# Spindle_Control.net
KiCad netlist of a schematic drawn in Altium Designer
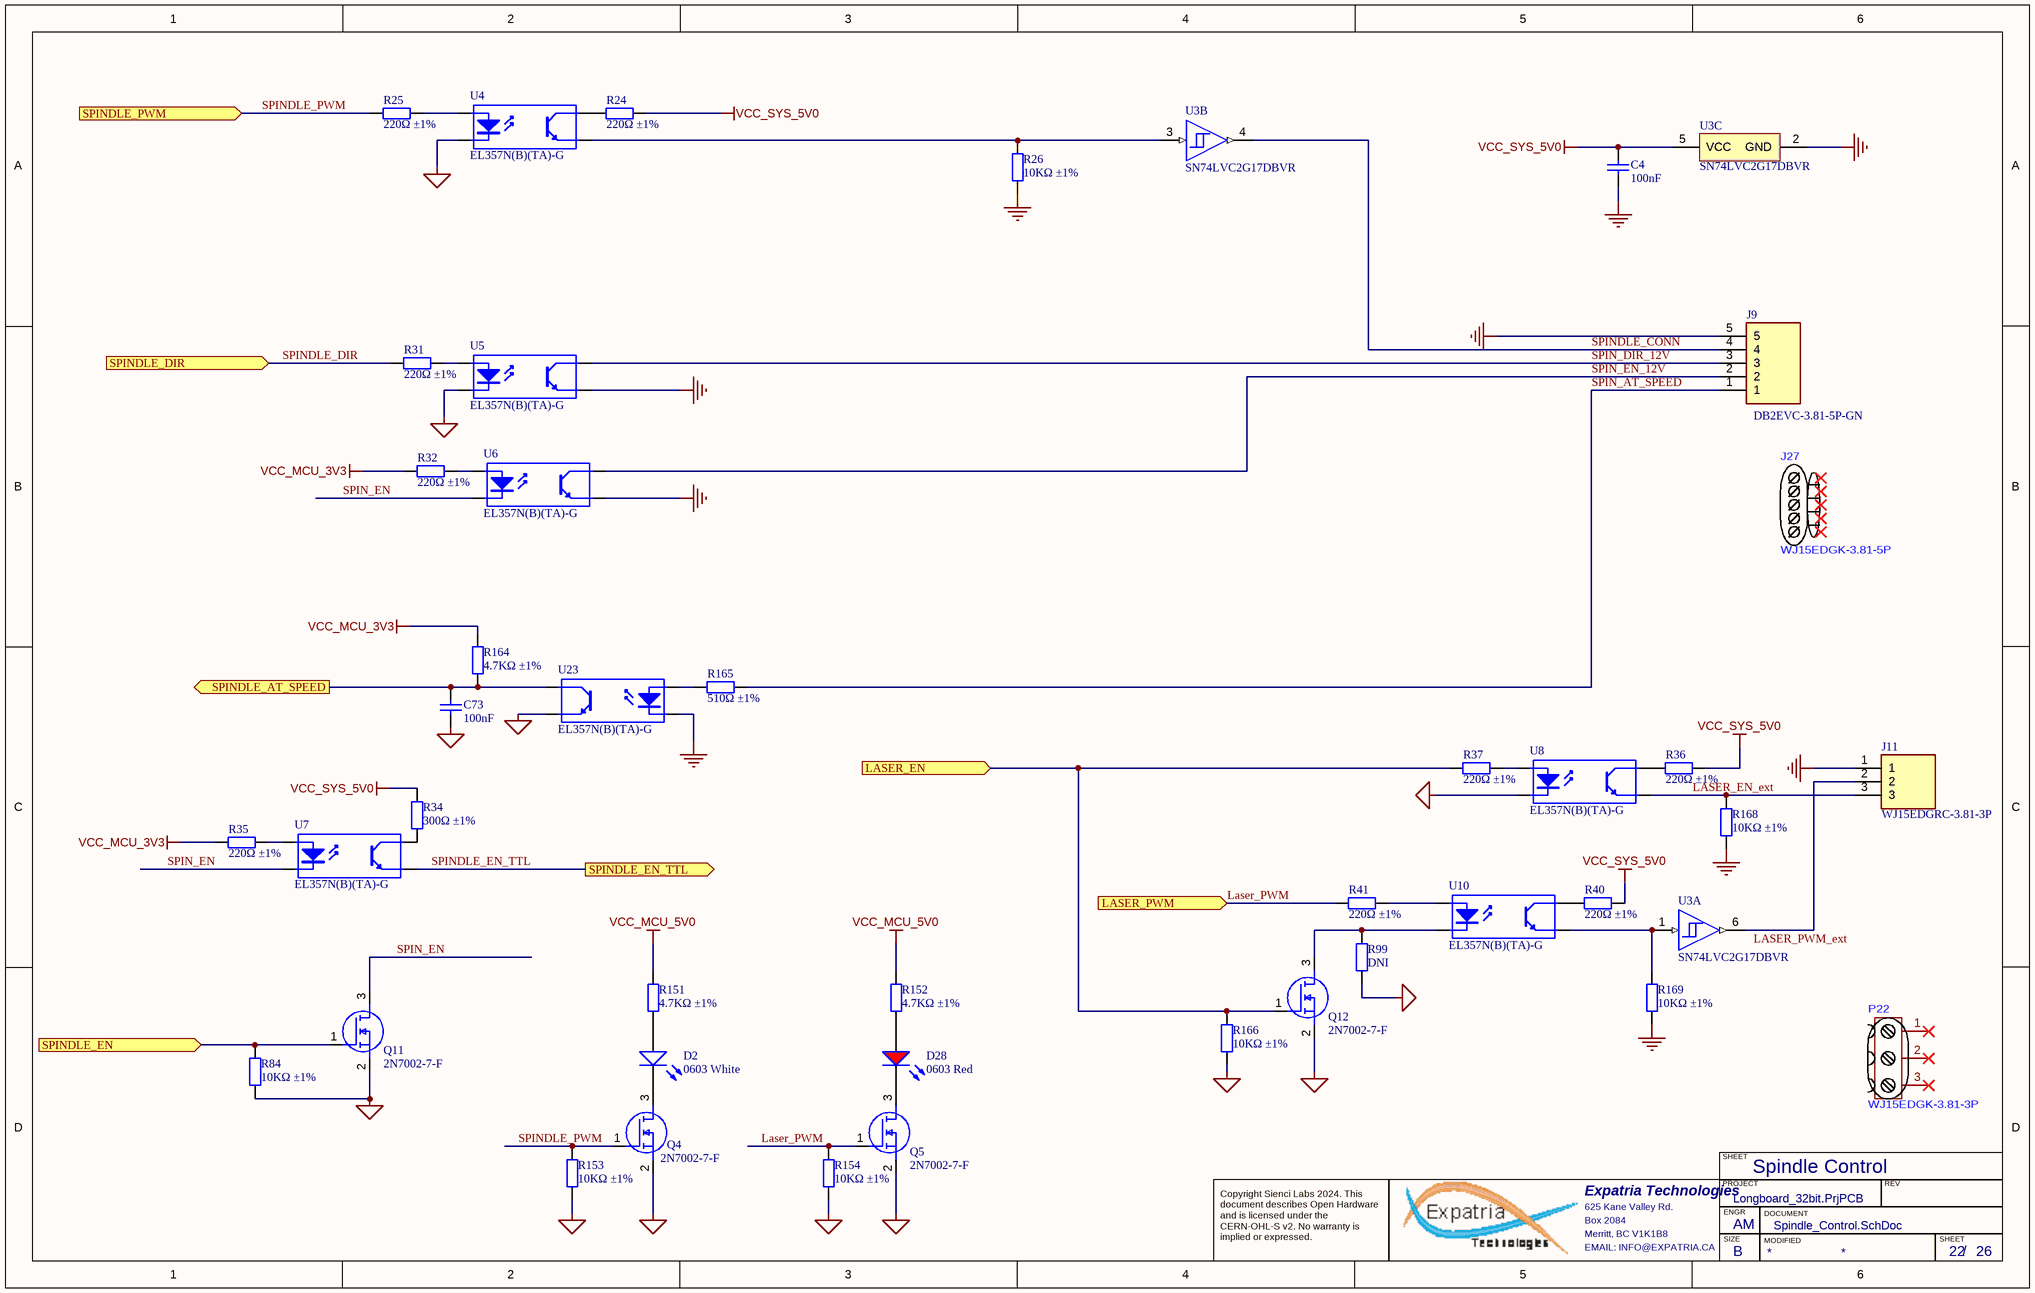
[diagram p0: Spindle_Control.SchDoc]

(export (version "E")
  (design (tool "Eeschema 10.0.6"))
  (components
    (comp (ref "C4")
      (value "100nF")
      (footprint "0603_C")
      (description "50V 100nF X7R ±10% 0603 Multilayer Ceramic Capacitors MLCC - SMD/SMT ROHS")
      (fields
        (field (name "MANUFACTURER") "YAGEO")
        (field (name "MANUFACTURER PART NUMBER") "CC0603KRX7R9BB104")
      )
      (libsource (lib "Sienci_Labs") (part "0603 100nF (104) 10% 50V"))
    )
    (comp (ref "C73")
      (value "100nF")
      (footprint "0402_C")
      (description "16V 100nF X7R ±10% 0402 Multilayer Ceramic Capacitors MLCC - SMD/SMT ROHS")
      (fields (field (name "MANUFACTURER") "Samsung Electro-Mechanics") (field (name "TOLERANCE") "10%"))
      (libsource (lib "Sienci_Labs") (part "0402 100nF (104) 10% 16V"))
    )
    (comp (ref "D2")
      (value "0603 White")
      (footprint "0603_LED_S1 - white")
      (description "LED")
      (fields
        (field (name "MANUFACTURER PART NUMBER") "19-217UWD/S365-2/TR8")
        (field (name "MANUFACTURER") "Everlight Elec")
      )
      (libsource (lib "Sienci_Labs") (part "19-217UWD/S365-2/TR8"))
    )
    (comp (ref "D28")
      (value "0603 Red")
      (footprint "0603_LED_S1")
      (fields
        (field (name "MANUFACTURER") "Everlight Elec")
        (field (name "MANUFACTURER PART NUMBER") "19-213SURC/S530-A3/TR8")
      )
      (libsource (lib "Sienci_Labs") (part "19-213SURC/S530-A3/TR8"))
    )
    (comp (ref "J9")
      (value "DB2EVC-3.81-5P-GN")
      (footprint "CONN-TH_5P-P3.81_DB2EVC-3.81-5P")
      (description "3.81mm Green Board Edge/Receptacle-Close Push-Pull,P=3.81mm Pluggable System Terminal Block ROHS")
      (fields (field (name "MANUFACTURER") "DIBO"))
      (libsource (lib "Sienci_Labs") (part "DB2EVC-3.81-5P-GN"))
    )
    (comp (ref "J11")
      (value "WJ15EDGRC-3.81-3P")
      (footprint "SHDRRA3W85P0X381_1X3_1231X915X720P")
      (description "3.81mm Green Board Edge/Receptacle-Close Push-Pull,P=3.81mm Pluggable System Terminal Block ROHS")
      (fields (field (name "MANUFACTURER") "Ningbo Kangnex"))
      (libsource (lib "Sienci_Labs") (part "WJ15EDGRC-3.81-3P"))
    )
    (comp (ref "J27")
      (value "WJ15EDGK-3.81-5P")
      (description "3.81mm Green Plug P=3.81mm Pluggable System Terminal Block ROHS")
      (fields (field (name "MANUFACTURER") "Ningbo Kangnex Elec"))
      (libsource (lib "Sienci_Labs") (part "WJ15EDGK-3.81-5P"))
    )
    (comp (ref "P22")
      (value "WJ15EDGK-3.81-3P")
      (description "3.81mm Green Plug P=3.81mm Pluggable System Terminal Block ROHS")
      (fields (field (name "MANUFACTURER") "Ningbo"))
      (libsource (lib "Sienci_Labs") (part "WJ15EDGK-3.81-3P"))
    )
    (comp (ref "Q4")
      (value "2N7002-7-F")
      (footprint "SOT-23(SOT-23-3)")
      (description "60V 115mA 7.5Ω@5V,50mA 370mW N Channel SOT-23 MOSFETs ROHS")
      (fields (field (name "MANUFACTURER") "Diodes Inc.") (field (name "MOUSER PART NUMBER") "621-2N7002-F"))
      (libsource (lib "Sienci_Labs") (part "2N7002-7-F"))
    )
    (comp (ref "Q5")
      (value "2N7002-7-F")
      (footprint "SOT-23(SOT-23-3)")
      (description "60V 115mA 7.5Ω@5V,50mA 370mW N Channel SOT-23 MOSFETs ROHS")
      (fields (field (name "MANUFACTURER") "Diodes Inc.") (field (name "MOUSER PART NUMBER") "621-2N7002-F"))
      (libsource (lib "Sienci_Labs") (part "2N7002-7-F"))
    )
    (comp (ref "Q11")
      (value "2N7002-7-F")
      (footprint "SOT-23(SOT-23-3)")
      (description "60V 115mA 7.5Ω@5V,50mA 370mW N Channel SOT-23 MOSFETs ROHS")
      (fields (field (name "MANUFACTURER") "Diodes Inc.") (field (name "MOUSER PART NUMBER") "621-2N7002-F"))
      (libsource (lib "Sienci_Labs") (part "2N7002-7-F"))
    )
    (comp (ref "Q12")
      (value "2N7002-7-F")
      (footprint "SOT-23(SOT-23-3)")
      (description "60V 115mA 7.5Ω@5V,50mA 370mW N Channel SOT-23 MOSFETs ROHS")
      (fields (field (name "MANUFACTURER") "Diodes Inc.") (field (name "MOUSER PART NUMBER") "621-2N7002-F"))
      (libsource (lib "Sienci_Labs") (part "2N7002-7-F"))
    )
    (comp (ref "R24")
      (value "220Ω ±1%")
      (footprint "0402_R")
      (description "Chip resistor")
      (fields
        (field (name "MANUFACTURER") "Uniroyal Elec")
        (field (name "MANUFACTURER PART NUMBER") "0402WGF2200TCE")
      )
      (libsource (lib "RES") (part "0402 220R (2200) 1%"))
    )
    (comp (ref "R25")
      (value "220Ω ±1%")
      (footprint "0402_R")
      (description "Chip resistor")
      (fields
        (field (name "MANUFACTURER") "Uniroyal Elec")
        (field (name "MANUFACTURER PART NUMBER") "0402WGF2200TCE")
      )
      (libsource (lib "RES") (part "0402 220R (2200) 1%"))
    )
    (comp (ref "R26")
      (value "10KΩ ±1%")
      (footprint "0402_R")
      (description "Chip resistor")
      (fields
        (field (name "MANUFACTURER") "Uniroyal Elec")
        (field (name "MANUFACTURER PART NUMBER") "0402WGF1002TCE")
      )
      (libsource (lib "RES") (part "0402 10K (1002) 1%"))
    )
    (comp (ref "R31")
      (value "220Ω ±1%")
      (footprint "0402_R")
      (description "Chip resistor")
      (fields
        (field (name "MANUFACTURER") "Uniroyal Elec")
        (field (name "MANUFACTURER PART NUMBER") "0402WGF2200TCE")
      )
      (libsource (lib "RES") (part "0402 220R (2200) 1%"))
    )
    (comp (ref "R32")
      (value "220Ω ±1%")
      (footprint "0402_R")
      (description "Chip resistor")
      (fields
        (field (name "MANUFACTURER") "Uniroyal Elec")
        (field (name "MANUFACTURER PART NUMBER") "0402WGF2200TCE")
      )
      (libsource (lib "RES") (part "0402 220R (2200) 1%"))
    )
    (comp (ref "R34")
      (value "300Ω ±1%")
      (footprint "0603_R")
      (description "Chip resistor")
      (fields
        (field (name "MANUFACTURER") "Uniroyal Elec")
        (field (name "MANUFACTURER PART NUMBER") "0603WAF3000T5E")
      )
      (libsource (lib "RES") (part "0603 300R (3000) 1%"))
    )
    (comp (ref "R35")
      (value "220Ω ±1%")
      (footprint "0402_R")
      (description "Chip resistor")
      (fields
        (field (name "MANUFACTURER") "Uniroyal Elec")
        (field (name "MANUFACTURER PART NUMBER") "0402WGF2200TCE")
      )
      (libsource (lib "RES") (part "0402 220R (2200) 1%"))
    )
    (comp (ref "R36")
      (value "220Ω ±1%")
      (footprint "0402_R")
      (description "Chip resistor")
      (fields
        (field (name "MANUFACTURER") "Uniroyal Elec")
        (field (name "MANUFACTURER PART NUMBER") "0402WGF2200TCE")
      )
      (libsource (lib "RES") (part "0402 220R (2200) 1%"))
    )
    (comp (ref "R37")
      (value "220Ω ±1%")
      (footprint "0402_R")
      (description "Chip resistor")
      (fields
        (field (name "MANUFACTURER") "Uniroyal Elec")
        (field (name "MANUFACTURER PART NUMBER") "0402WGF2200TCE")
      )
      (libsource (lib "RES") (part "0402 220R (2200) 1%"))
    )
    (comp (ref "R40")
      (value "220Ω ±1%")
      (footprint "0402_R")
      (description "Chip resistor")
      (fields
        (field (name "MANUFACTURER") "Uniroyal Elec")
        (field (name "MANUFACTURER PART NUMBER") "0402WGF2200TCE")
      )
      (libsource (lib "") (part "0402 220R (2200) 1%_1"))
    )
    (comp (ref "R41")
      (value "220Ω ±1%")
      (footprint "0402_R")
      (description "Chip resistor")
      (fields
        (field (name "MANUFACTURER") "Uniroyal Elec")
        (field (name "MANUFACTURER PART NUMBER") "0402WGF2200TCE")
      )
      (libsource (lib "RES") (part "0402 220R (2200) 1%"))
    )
    (comp (ref "R84")
      (value "10KΩ ±1%")
      (footprint "0402_R")
      (description "Chip resistor")
      (fields
        (field (name "MANUFACTURER") "Uniroyal Elec")
        (field (name "MANUFACTURER PART NUMBER") "0402WGF1002TCE")
      )
      (libsource (lib "RES") (part "0402 10K (1002) 1%"))
    )
    (comp (ref "R99")
      (value "DNI")
      (footprint "0603_R")
      (description "Chip resistor")
      (fields
        (field (name "MANUFACTURER") "Uniroyal Elec")
        (field (name "MANUFACTURER PART NUMBER") "0603WAF0000T5E")
      )
      (libsource (lib "RES") (part "0603 0R (0R0) 1%"))
    )
    (comp (ref "R151")
      (value "4.7KΩ ±1%")
      (footprint "0402_R")
      (description "Chip resistor")
      (fields
        (field (name "MANUFACTURER") "Uniroyal Elec")
        (field (name "MANUFACTURER PART NUMBER") "0402WGF4701TCE")
      )
      (libsource (lib "RES") (part "0402 4.7K (4701) 1%"))
    )
    (comp (ref "R152")
      (value "4.7KΩ ±1%")
      (footprint "0402_R")
      (description "Chip resistor")
      (fields
        (field (name "MANUFACTURER") "Uniroyal Elec")
        (field (name "MANUFACTURER PART NUMBER") "0402WGF4701TCE")
      )
      (libsource (lib "RES") (part "0402 4.7K (4701) 1%"))
    )
    (comp (ref "R153")
      (value "10KΩ ±1%")
      (footprint "0402_R")
      (description "Chip resistor")
      (fields
        (field (name "MANUFACTURER") "Uniroyal Elec")
        (field (name "MANUFACTURER PART NUMBER") "0402WGF1002TCE")
      )
      (libsource (lib "RES") (part "0402 10K (1002) 1%"))
    )
    (comp (ref "R154")
      (value "10KΩ ±1%")
      (footprint "0402_R")
      (description "Chip resistor")
      (fields
        (field (name "MANUFACTURER") "Uniroyal Elec")
        (field (name "MANUFACTURER PART NUMBER") "0402WGF1002TCE")
      )
      (libsource (lib "RES") (part "0402 10K (1002) 1%"))
    )
    (comp (ref "R164")
      (value "4.7KΩ ±1%")
      (footprint "0402_R")
      (description "Chip resistor")
      (fields (field (name "MANUFACTURER") "Uniroyal Elec") (field (name "POWER") "1/16W"))
      (libsource (lib "") (part "0402 4.7K (4701) 1%_1"))
    )
    (comp (ref "R165")
      (value "510Ω ±1%")
      (footprint "0402_R")
      (description "Chip resistor")
      (fields
        (field (name "MANUFACTURER") "Uniroyal Elec")
        (field (name "MANUFACTURER PART NUMBER") "0402WGF5100TCE")
      )
      (libsource (lib "RES") (part "0402 510R (5100) 1%"))
    )
    (comp (ref "R166")
      (value "10KΩ ±1%")
      (footprint "0402_R")
      (description "Chip resistor")
      (fields
        (field (name "MANUFACTURER") "Uniroyal Elec")
        (field (name "MANUFACTURER PART NUMBER") "0402WGF1002TCE")
      )
      (libsource (lib "RES") (part "0402 10K (1002) 1%"))
    )
    (comp (ref "R168")
      (value "10KΩ ±1%")
      (footprint "0402_R")
      (description "Chip resistor")
      (fields
        (field (name "MANUFACTURER") "Uniroyal Elec")
        (field (name "MANUFACTURER PART NUMBER") "0402WGF1002TCE")
      )
      (libsource (lib "RES") (part "0402 10K (1002) 1%"))
    )
    (comp (ref "R169")
      (value "10KΩ ±1%")
      (footprint "0402_R")
      (description "Chip resistor")
      (fields
        (field (name "MANUFACTURER") "Uniroyal Elec")
        (field (name "MANUFACTURER PART NUMBER") "0402WGF1002TCE")
      )
      (libsource (lib "RES") (part "0402 10K (1002) 1%"))
    )
    (comp (ref "U3")
      (value "SN74LVC2G17DBVR")
      (footprint "DBV0006A_N")
      (description "Dual Schmitt-Trigger Buffer, DBV0006A, LARGE T&R")
      (fields
        (field (name "GENERIC PART NUMBER") "SN74LVC2G17")
        (field (name "MANUFACTURER") "Texas Instruments")
      )
      (libsource (lib "Altium Content Vault") (part "TI-SN74XXX2GXXX-6_A-SCHMITT"))
    )
    (comp (ref "U4")
      (value "EL357N(B)(TA)-G")
      (footprint "SOP-4_P2.54")
      (description "80V 3750V 50mA 0.1V@1mA,20mA 1 6V 1.2V DC SOP-4-2.54mm Optocouplers - Phototransistor Output ROHS")
      (fields (field (name "MANUFACTURER") "Everlight Elec"))
      (libsource (lib "PrintNC_GRBLHAL_Breakout") (part "EL357N(B)(TA)-G_[C6649]"))
    )
    (comp (ref "U5")
      (value "EL357N(B)(TA)-G")
      (footprint "Miscellaneous Devices LC:SOP-4_P2.54")
      (description "80V 3750V 50mA 0.1V@1mA,20mA 1 6V 1.2V DC SOP-4-2.54mm Optocouplers - Phototransistor Output ROHS")
      (fields (field (name "MANUFACTURER") "Everlight Elec"))
      (libsource (lib "PrintNC_GRBLHAL_Breakout") (part "EL357N(B)(TA)-G_[C6649]"))
    )
    (comp (ref "U6")
      (value "EL357N(B)(TA)-G")
      (footprint "Miscellaneous Devices LC:SOP-4_P2.54")
      (description "80V 3750V 50mA 0.1V@1mA,20mA 1 6V 1.2V DC SOP-4-2.54mm Optocouplers - Phototransistor Output ROHS")
      (fields (field (name "MANUFACTURER") "Everlight Elec"))
      (libsource (lib "PrintNC_GRBLHAL_Breakout") (part "EL357N(B)(TA)-G_[C6649]"))
    )
    (comp (ref "U7")
      (value "EL357N(B)(TA)-G")
      (footprint "Miscellaneous Devices LC:SOP-4_P2.54")
      (description "80V 3750V 50mA 0.1V@1mA,20mA 1 6V 1.2V DC SOP-4-2.54mm Optocouplers - Phototransistor Output ROHS")
      (fields (field (name "MANUFACTURER") "Everlight Elec"))
      (libsource (lib "IC") (part "EL357N(B)(TA)-G_[C6649]"))
    )
    (comp (ref "U8")
      (value "EL357N(B)(TA)-G")
      (footprint "Miscellaneous Devices LC:SOP-4_P2.54")
      (description "80V 3750V 50mA 0.1V@1mA,20mA 1 6V 1.2V DC SOP-4-2.54mm Optocouplers - Phototransistor Output ROHS")
      (fields (field (name "MANUFACTURER") "Everlight Elec"))
      (libsource (lib "IC") (part "EL357N(B)(TA)-G_[C6649]"))
    )
    (comp (ref "U10")
      (value "EL357N(B)(TA)-G")
      (footprint "Miscellaneous Devices LC:SOP-4_P2.54")
      (description "80V 3750V 50mA 0.1V@1mA,20mA 1 6V 1.2V DC SOP-4-2.54mm Optocouplers - Phototransistor Output ROHS")
      (fields (field (name "MANUFACTURER") "Everlight Elec"))
      (libsource (lib "IC") (part "EL357N(B)(TA)-G_[C6649]"))
    )
    (comp (ref "U23")
      (value "EL357N(B)(TA)-G")
      (footprint "SOP-4_P2.54")
      (description "80V 3750V 50mA 0.1V@1mA,20mA 1 6V 1.2V DC SOP-4-2.54mm Optocouplers - Phototransistor Output ROHS")
      (fields (field (name "MANUFACTURER") "Everlight Elec"))
      (libsource (lib "IC") (part "EL357N(B)(TA)-G_[C6649]"))
    )
  )
  (nets
    (net (code "1") (name "/LASER_EN") (class "Default")
      (node (ref "Q12") (pin "1") (pinfunction "G_1") (pintype "passive"))
      (node (ref "R166") (pin "2") (pinfunction "2_2") (pintype "passive"))
      (node (ref "R37") (pin "1") (pinfunction "1_1") (pintype "passive"))
    )
    (net (code "2") (name "/LASER_EN_ext") (class "Default")
      (node (ref "J11") (pin "3") (pinfunction "3_3") (pintype "passive"))
      (node (ref "R168") (pin "2") (pinfunction "2_2") (pintype "passive"))
      (node (ref "U8") (pin "3") (pinfunction "E_3") (pintype "passive"))
    )
    (net (code "3") (name "/LASER_PWM_ext") (class "Default")
      (node (ref "J11") (pin "2") (pinfunction "2_2") (pintype "passive"))
      (node (ref "U3") (pin "6") (pinfunction "1Y_6") (pintype "output"))
    )
    (net (code "4") (name "/Laser_PWM") (class "Default")
      (node (ref "Q5") (pin "1") (pinfunction "G_1") (pintype "passive"))
      (node (ref "R154") (pin "2") (pinfunction "2_2") (pintype "passive"))
      (node (ref "R41") (pin "1") (pinfunction "1_1") (pintype "passive"))
    )
    (net (code "5") (name "/SPINDLE_AT_SPEED") (class "Default")
      (node (ref "C73") (pin "2") (pinfunction "2_2") (pintype "passive"))
      (node (ref "R164") (pin "2") (pinfunction "2_2") (pintype "passive"))
      (node (ref "U23") (pin "4") (pinfunction "C_4") (pintype "passive"))
    )
    (net (code "6") (name "/SPINDLE_CONN") (class "Default")
      (node (ref "J9") (pin "4") (pinfunction "4_4") (pintype "passive"))
      (node (ref "U3") (pin "4") (pinfunction "2Y_4") (pintype "output"))
    )
    (net (code "7") (name "/SPINDLE_DIR") (class "Default")
      (node (ref "R31") (pin "1") (pinfunction "1_1") (pintype "passive"))
    )
    (net (code "8") (name "/SPINDLE_EN") (class "Default")
      (node (ref "Q11") (pin "1") (pinfunction "G_1") (pintype "passive"))
      (node (ref "R84") (pin "2") (pinfunction "2_2") (pintype "passive"))
    )
    (net (code "9") (name "/SPINDLE_EN_TTL") (class "Default")
      (node (ref "U7") (pin "3") (pinfunction "E_3") (pintype "passive"))
    )
    (net (code "10") (name "/SPINDLE_PWM") (class "Default")
      (node (ref "Q4") (pin "1") (pinfunction "G_1") (pintype "passive"))
      (node (ref "R153") (pin "2") (pinfunction "2_2") (pintype "passive"))
      (node (ref "R25") (pin "1") (pinfunction "1_1") (pintype "passive"))
    )
    (net (code "11") (name "/SPIN_AT_SPEED") (class "Default")
      (node (ref "J9") (pin "1") (pinfunction "1_1") (pintype "passive"))
      (node (ref "R165") (pin "1") (pinfunction "1_1") (pintype "passive"))
    )
    (net (code "12") (name "/SPIN_DIR_12V") (class "Default")
      (node (ref "J9") (pin "3") (pinfunction "3_3") (pintype "passive"))
      (node (ref "U5") (pin "4") (pinfunction "C_4") (pintype "passive"))
    )
    (net (code "13") (name "/SPIN_EN") (class "Default")
      (node (ref "Q11") (pin "3") (pinfunction "D_3") (pintype "passive"))
      (node (ref "U6") (pin "2") (pinfunction "K_2") (pintype "passive"))
      (node (ref "U7") (pin "2") (pinfunction "K_2") (pintype "passive"))
    )
    (net (code "14") (name "/SPIN_EN_12V") (class "Default")
      (node (ref "J9") (pin "2") (pinfunction "2_2") (pintype "passive"))
      (node (ref "U6") (pin "4") (pinfunction "C_4") (pintype "passive"))
    )
    (net (code "15") (name "GND") (class "Default")
      (node (ref "C4") (pin "1") (pinfunction "1_1") (pintype "passive"))
      (node (ref "J11") (pin "1") (pinfunction "1_1") (pintype "passive"))
      (node (ref "J9") (pin "5") (pinfunction "5_5") (pintype "passive"))
      (node (ref "R168") (pin "1") (pinfunction "1_1") (pintype "passive"))
      (node (ref "R169") (pin "1") (pinfunction "1_1") (pintype "passive"))
      (node (ref "R26") (pin "1") (pinfunction "1_1") (pintype "passive"))
      (node (ref "U23") (pin "2") (pinfunction "K_2") (pintype "passive"))
      (node (ref "U3") (pin "2") (pinfunction "GND_2") (pintype "power_in"))
      (node (ref "U5") (pin "3") (pinfunction "E_3") (pintype "passive"))
      (node (ref "U6") (pin "3") (pinfunction "E_3") (pintype "passive"))
    )
    (net (code "16") (name "MCU_GND") (class "Default")
      (node (ref "C73") (pin "1") (pinfunction "1_1") (pintype "passive"))
      (node (ref "Q11") (pin "2") (pinfunction "S_2") (pintype "passive"))
      (node (ref "Q12") (pin "2") (pinfunction "S_2") (pintype "passive"))
      (node (ref "Q4") (pin "2") (pinfunction "S_2") (pintype "passive"))
      (node (ref "Q5") (pin "2") (pinfunction "S_2") (pintype "passive"))
      (node (ref "R153") (pin "1") (pinfunction "1_1") (pintype "passive"))
      (node (ref "R154") (pin "1") (pinfunction "1_1") (pintype "passive"))
      (node (ref "R166") (pin "1") (pinfunction "1_1") (pintype "passive"))
      (node (ref "R84") (pin "1") (pinfunction "1_1") (pintype "passive"))
      (node (ref "R99") (pin "2") (pinfunction "2_2") (pintype "passive"))
      (node (ref "U23") (pin "3") (pinfunction "E_3") (pintype "passive"))
      (node (ref "U4") (pin "2") (pinfunction "K_2") (pintype "passive"))
      (node (ref "U5") (pin "2") (pinfunction "K_2") (pintype "passive"))
      (node (ref "U8") (pin "2") (pinfunction "K_2") (pintype "passive"))
    )
    (net (code "17") (name "Net-(D2-PadA)") (class "Default")
      (node (ref "D2") (pin "A") (pinfunction "A_A") (pintype "passive"))
      (node (ref "R151") (pin "1") (pinfunction "1_1") (pintype "passive"))
    )
    (net (code "18") (name "Net-(D28-PadA)") (class "Default")
      (node (ref "D28") (pin "A") (pinfunction "A_A") (pintype "passive"))
      (node (ref "R152") (pin "1") (pinfunction "1_1") (pintype "passive"))
    )
    (net (code "19") (name "Net-(Q4-D)") (class "Default")
      (node (ref "D2") (pin "K") (pinfunction "K_K") (pintype "passive"))
      (node (ref "Q4") (pin "3") (pinfunction "D_3") (pintype "passive"))
    )
    (net (code "20") (name "Net-(Q5-D)") (class "Default")
      (node (ref "D28") (pin "K") (pinfunction "K_K") (pintype "passive"))
      (node (ref "Q5") (pin "3") (pinfunction "D_3") (pintype "passive"))
    )
    (net (code "21") (name "Net-(Q12-D)") (class "Default")
      (node (ref "Q12") (pin "3") (pinfunction "D_3") (pintype "passive"))
      (node (ref "R99") (pin "1") (pinfunction "1_1") (pintype "passive"))
      (node (ref "U10") (pin "2") (pinfunction "K_2") (pintype "passive"))
    )
    (net (code "22") (name "Net-(U3B-2A)") (class "Default")
      (node (ref "R26") (pin "2") (pinfunction "2_2") (pintype "passive"))
      (node (ref "U3") (pin "3") (pinfunction "2A_3") (pintype "input"))
      (node (ref "U4") (pin "3") (pinfunction "E_3") (pintype "passive"))
    )
    (net (code "23") (name "Net-(U4-A)") (class "Default")
      (node (ref "R25") (pin "2") (pinfunction "2_2") (pintype "passive"))
      (node (ref "U4") (pin "1") (pinfunction "A_1") (pintype "passive"))
    )
    (net (code "24") (name "Net-(U4-C)") (class "Default")
      (node (ref "R24") (pin "1") (pinfunction "1_1") (pintype "passive"))
      (node (ref "U4") (pin "4") (pinfunction "C_4") (pintype "passive"))
    )
    (net (code "25") (name "Net-(U5-A)") (class "Default")
      (node (ref "R31") (pin "2") (pinfunction "2_2") (pintype "passive"))
      (node (ref "U5") (pin "1") (pinfunction "A_1") (pintype "passive"))
    )
    (net (code "26") (name "Net-(U6-A)") (class "Default")
      (node (ref "R32") (pin "2") (pinfunction "2_2") (pintype "passive"))
      (node (ref "U6") (pin "1") (pinfunction "A_1") (pintype "passive"))
    )
    (net (code "27") (name "Net-(U7-A)") (class "Default")
      (node (ref "R35") (pin "2") (pinfunction "2_2") (pintype "passive"))
      (node (ref "U7") (pin "1") (pinfunction "A_1") (pintype "passive"))
    )
    (net (code "28") (name "Net-(U7-C)") (class "Default")
      (node (ref "R34") (pin "2") (pinfunction "2_2") (pintype "passive"))
      (node (ref "U7") (pin "4") (pinfunction "C_4") (pintype "passive"))
    )
    (net (code "29") (name "Net-(U8-A)") (class "Default")
      (node (ref "R37") (pin "2") (pinfunction "2_2") (pintype "passive"))
      (node (ref "U8") (pin "1") (pinfunction "A_1") (pintype "passive"))
    )
    (net (code "30") (name "Net-(U8-C)") (class "Default")
      (node (ref "R36") (pin "1") (pinfunction "1_1") (pintype "passive"))
      (node (ref "U8") (pin "4") (pinfunction "C_4") (pintype "passive"))
    )
    (net (code "31") (name "Net-(U10-A)") (class "Default")
      (node (ref "R41") (pin "2") (pinfunction "2_2") (pintype "passive"))
      (node (ref "U10") (pin "1") (pinfunction "A_1") (pintype "passive"))
    )
    (net (code "32") (name "Net-(U10-C)") (class "Default")
      (node (ref "R40") (pin "2") (pinfunction "2_2") (pintype "passive"))
      (node (ref "U10") (pin "4") (pinfunction "C_4") (pintype "passive"))
    )
    (net (code "33") (name "Net-(U10-E)") (class "Default")
      (node (ref "R169") (pin "2") (pinfunction "2_2") (pintype "passive"))
      (node (ref "U10") (pin "3") (pinfunction "E_3") (pintype "passive"))
      (node (ref "U3") (pin "1") (pinfunction "1A_1") (pintype "input"))
    )
    (net (code "34") (name "Net-(U23-A)") (class "Default")
      (node (ref "R165") (pin "2") (pinfunction "2_2") (pintype "passive"))
      (node (ref "U23") (pin "1") (pinfunction "A_1") (pintype "passive"))
    )
    (net (code "35") (name "VCC_MCU_3V3") (class "Default")
      (node (ref "R164") (pin "1") (pinfunction "1_1") (pintype "passive"))
      (node (ref "R32") (pin "1") (pinfunction "1_1") (pintype "passive"))
      (node (ref "R35") (pin "1") (pinfunction "1_1") (pintype "passive"))
    )
    (net (code "36") (name "VCC_MCU_5V0") (class "Default")
      (node (ref "R151") (pin "2") (pinfunction "2_2") (pintype "passive"))
      (node (ref "R152") (pin "2") (pinfunction "2_2") (pintype "passive"))
    )
    (net (code "37") (name "VCC_SYS_5V0") (class "Default")
      (node (ref "C4") (pin "2") (pinfunction "2_2") (pintype "passive"))
      (node (ref "R24") (pin "2") (pinfunction "2_2") (pintype "passive"))
      (node (ref "R34") (pin "1") (pinfunction "1_1") (pintype "passive"))
      (node (ref "R36") (pin "2") (pinfunction "2_2") (pintype "passive"))
      (node (ref "R40") (pin "1") (pinfunction "1_1") (pintype "passive"))
      (node (ref "U3") (pin "5") (pinfunction "VCC_5") (pintype "power_in"))
    )
    (net (code "38") (name "unconnected-(P22-Pad1)") (class "Default")
      (node (ref "P22") (pin "1") (pinfunction "1_1") (pintype "passive+no_connect"))
    )
    (net (code "39") (name "unconnected-(P22-Pad2)") (class "Default")
      (node (ref "P22") (pin "2") (pinfunction "2_2") (pintype "passive+no_connect"))
    )
    (net (code "40") (name "unconnected-(P22-Pad3)") (class "Default")
      (node (ref "P22") (pin "3") (pinfunction "3_3") (pintype "passive+no_connect"))
    )
  )
)
